# RS-485-Interface-Unit.net
KiCad netlist of a schematic drawn in EAGLE
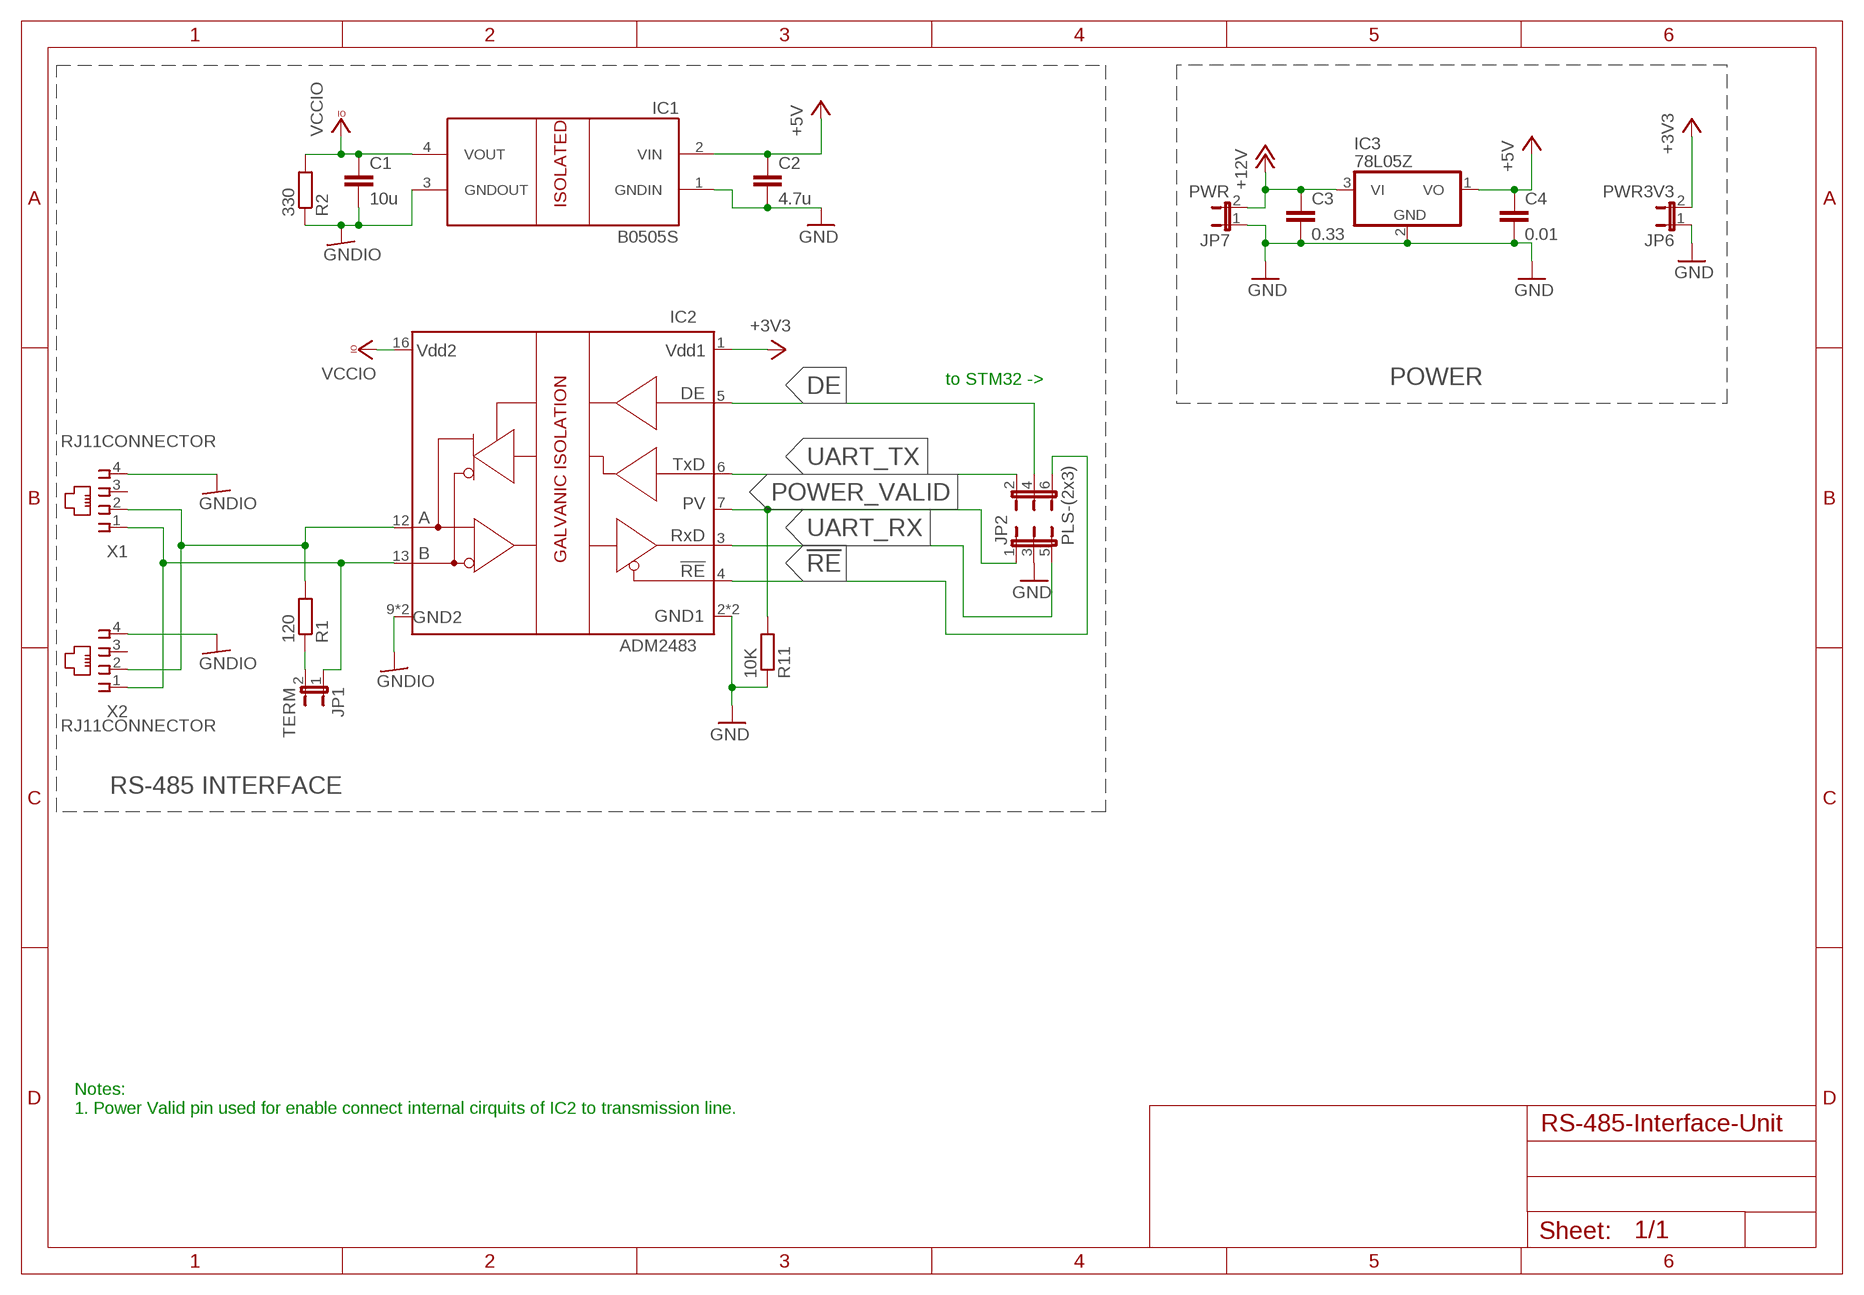
[diagram p0: schematic, sheet 1]

(export (version "E")
  (design (tool "Eeschema 10.0.6"))
  (components
    (comp (ref "C1")
      (value "10u")
      (footprint "eagle-import:C0805")
      (libsource (lib "eagle-import") (part "C-EUC0805"))
    )
    (comp (ref "C2")
      (value "4.7u")
      (footprint "eagle-import:C0805")
      (libsource (lib "eagle-import") (part "C-EUC0805"))
    )
    (comp (ref "C3")
      (value "0.33")
      (footprint "eagle-import:C2012")
      (libsource (lib "eagle-import") (part "C-EUC2012"))
    )
    (comp (ref "C4")
      (value "0.01")
      (footprint "eagle-import:C2012")
      (libsource (lib "eagle-import") (part "C-EUC2012"))
    )
    (comp (ref "IC1")
      (value "B0505S")
      (footprint "eagle-import:SC_PACKAGE")
      (libsource (lib "eagle-import") (part "B0505S"))
    )
    (comp (ref "IC2")
      (value "ADM2483")
      (footprint "eagle-import:SO16W")
      (libsource (lib "eagle-import") (part "ADM2483"))
    )
    (comp (ref "IC3")
      (value "78L05Z")
      (footprint "eagle-import:TO92")
      (libsource (lib "eagle-import") (part "78ZL05"))
    )
    (comp (ref "JP1")
      (value "TERM")
      (footprint "eagle-import:JP1")
      (libsource (lib "eagle-import") (part "JP1E"))
    )
    (comp (ref "JP2")
      (value "PLS-(2х3)")
      (footprint "eagle-import:PLS-(2х3)")
      (libsource (lib "eagle-import") (part "PLS-(2х3)"))
    )
    (comp (ref "JP6")
      (value "PWR3V3")
      (footprint "eagle-import:JP1")
      (libsource (lib "eagle-import") (part "JP1E"))
    )
    (comp (ref "JP7")
      (value "PWR")
      (footprint "eagle-import:JP1")
      (libsource (lib "eagle-import") (part "JP1E"))
    )
    (comp (ref "R1")
      (value "120")
      (footprint "eagle-import:0204_7")
      (libsource (lib "eagle-import") (part "R-EU_0204/7"))
    )
    (comp (ref "R2")
      (value "330")
      (footprint "eagle-import:R0805")
      (libsource (lib "eagle-import") (part "R-EU_R0805"))
    )
    (comp (ref "R11")
      (value "10K")
      (footprint "eagle-import:R0805")
      (libsource (lib "eagle-import") (part "R-EU_R0805"))
    )
    (comp (ref "X1")
      (value "RJ11CONNECTOR")
      (footprint "eagle-import:RJ11_NONAME")
      (libsource (lib "eagle-import") (part "RJ11CONNECTOR"))
    )
    (comp (ref "X2")
      (value "RJ11CONNECTOR")
      (footprint "eagle-import:RJ11_NONAME")
      (libsource (lib "eagle-import") (part "RJ11CONNECTOR"))
    )
  )
  (nets
    (net (code "1") (name "+3V3") (class "Default")
      (node (ref "IC2") (pin "1") (pinfunction "VDD1_1") (pintype "power_in"))
      (node (ref "JP6") (pin "2") (pinfunction "2_2") (pintype "passive"))
    )
    (net (code "2") (name "+5V") (class "Default")
      (node (ref "C2") (pin "1") (pinfunction "1_1") (pintype "passive"))
      (node (ref "C4") (pin "1") (pinfunction "1_1") (pintype "passive"))
      (node (ref "IC1") (pin "2") (pinfunction "VIN_2") (pintype "power_in"))
      (node (ref "IC3") (pin "1") (pinfunction "VO_1") (pintype "passive"))
    )
    (net (code "3") (name "+12V") (class "Default")
      (node (ref "C3") (pin "1") (pinfunction "1_1") (pintype "passive"))
      (node (ref "IC3") (pin "3") (pinfunction "VI_3") (pintype "input"))
      (node (ref "JP7") (pin "2") (pinfunction "2_2") (pintype "passive"))
    )
    (net (code "4") (name "/~{RE}") (class "Default")
      (node (ref "IC2") (pin "4") (pinfunction "~{RE}_4") (pintype "input"))
      (node (ref "JP2") (pin "6") (pinfunction "6_6") (pintype "passive"))
    )
    (net (code "5") (name "DE") (class "Default")
      (node (ref "IC2") (pin "5") (pinfunction "DE_5") (pintype "input"))
      (node (ref "JP2") (pin "4") (pinfunction "4_4") (pintype "passive"))
    )
    (net (code "6") (name "GND") (class "Default")
      (node (ref "C2") (pin "2") (pinfunction "2_2") (pintype "passive"))
      (node (ref "C3") (pin "2") (pinfunction "2_2") (pintype "passive"))
      (node (ref "C4") (pin "2") (pinfunction "2_2") (pintype "passive"))
      (node (ref "IC1") (pin "1") (pinfunction "GNDIN_1") (pintype "power_in"))
      (node (ref "IC2") (pin "2") (pinfunction "GND1_2") (pintype "power_in"))
      (node (ref "IC2") (pin "8") (pinfunction "GND1_8") (pintype "power_in"))
      (node (ref "IC3") (pin "2") (pinfunction "GND_2") (pintype "passive"))
      (node (ref "JP2") (pin "3") (pinfunction "3_3") (pintype "passive"))
      (node (ref "JP6") (pin "1") (pinfunction "1_1") (pintype "passive"))
      (node (ref "JP7") (pin "1") (pinfunction "1_1") (pintype "passive"))
      (node (ref "R11") (pin "1") (pinfunction "1_1") (pintype "passive"))
    )
    (net (code "7") (name "GNDIO") (class "Default")
      (node (ref "C1") (pin "2") (pinfunction "2_2") (pintype "passive"))
      (node (ref "IC1") (pin "3") (pinfunction "GNDOUT_3") (pintype "power_in"))
      (node (ref "IC2") (pin "15") (pinfunction "GND2_15") (pintype "power_in"))
      (node (ref "IC2") (pin "9") (pinfunction "GND2_9") (pintype "power_in"))
      (node (ref "R2") (pin "1") (pinfunction "1_1") (pintype "passive"))
      (node (ref "X1") (pin "4") (pinfunction "4_4") (pintype "passive"))
      (node (ref "X2") (pin "4") (pinfunction "4_4") (pintype "passive"))
    )
    (net (code "8") (name "Net-(IC2-A)") (class "Default")
      (node (ref "IC2") (pin "12") (pinfunction "A_12") (pintype "passive"))
      (node (ref "R1") (pin "2") (pinfunction "2_2") (pintype "passive"))
      (node (ref "X1") (pin "2") (pinfunction "2_2") (pintype "passive"))
      (node (ref "X2") (pin "2") (pinfunction "2_2") (pintype "passive"))
    )
    (net (code "9") (name "Net-(IC2-B)") (class "Default")
      (node (ref "IC2") (pin "13") (pinfunction "B_13") (pintype "passive"))
      (node (ref "JP1") (pin "1") (pinfunction "1_1") (pintype "passive"))
      (node (ref "X1") (pin "1") (pinfunction "1_1") (pintype "passive"))
      (node (ref "X2") (pin "1") (pinfunction "1_1") (pintype "passive"))
    )
    (net (code "10") (name "Net-(JP1-Pad2)") (class "Default")
      (node (ref "JP1") (pin "2") (pinfunction "2_2") (pintype "passive"))
      (node (ref "R1") (pin "1") (pinfunction "1_1") (pintype "passive"))
    )
    (net (code "11") (name "POWER_VALID") (class "Default")
      (node (ref "IC2") (pin "7") (pinfunction "PV_7") (pintype "input"))
      (node (ref "JP2") (pin "1") (pinfunction "1_1") (pintype "passive"))
      (node (ref "R11") (pin "2") (pinfunction "2_2") (pintype "passive"))
    )
    (net (code "12") (name "UART_RX") (class "Default")
      (node (ref "IC2") (pin "3") (pinfunction "RXD_3") (pintype "output"))
      (node (ref "JP2") (pin "5") (pinfunction "5_5") (pintype "passive"))
    )
    (net (code "13") (name "UART_TX") (class "Default")
      (node (ref "IC2") (pin "6") (pinfunction "TXD_6") (pintype "input"))
      (node (ref "JP2") (pin "2") (pinfunction "2_2") (pintype "passive"))
    )
    (net (code "14") (name "VCCIO") (class "Default")
      (node (ref "C1") (pin "1") (pinfunction "1_1") (pintype "passive"))
      (node (ref "IC1") (pin "4") (pinfunction "VOUT_4") (pintype "power_in"))
      (node (ref "IC2") (pin "16") (pinfunction "VDD2_16") (pintype "power_in"))
      (node (ref "R2") (pin "2") (pinfunction "2_2") (pintype "passive"))
    )
    (net (code "15") (name "unconnected-(X1-Pad3)") (class "Default")
      (node (ref "X1") (pin "3") (pinfunction "3_3") (pintype "passive"))
    )
    (net (code "16") (name "unconnected-(X2-Pad3)") (class "Default")
      (node (ref "X2") (pin "3") (pinfunction "3_3") (pintype "passive"))
    )
  )
)
